# strobe_ds.net
KiCad netlist of a schematic drawn in EAGLE
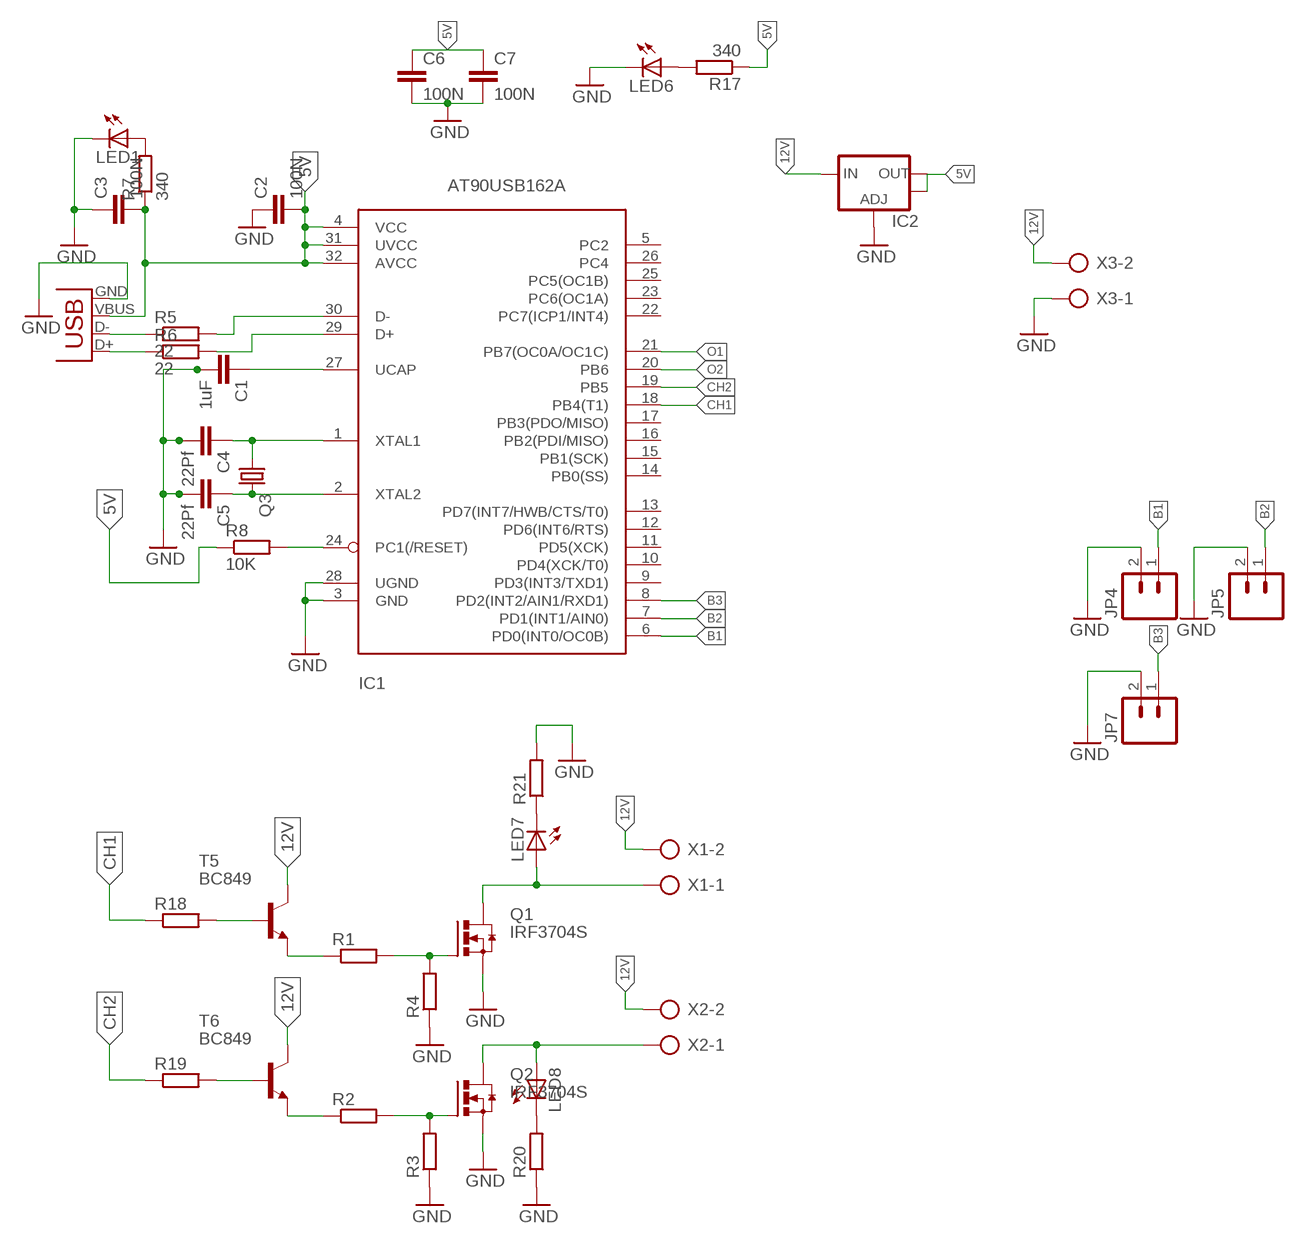
[diagram p0: schematic, sheet 1]

(export (version "E")
  (design (tool "Eeschema 10.0.6"))
  (components
    (comp (ref "C1")
      (value "1uF")
      (footprint "eagle-import:C0805")
      (libsource (lib "eagle-import") (part "C-EUC0805"))
    )
    (comp (ref "C2")
      (value "100N")
      (footprint "eagle-import:C0805")
      (libsource (lib "eagle-import") (part "C-EUC0805"))
    )
    (comp (ref "C3")
      (value "100N")
      (footprint "eagle-import:C0805")
      (libsource (lib "eagle-import") (part "C-EUC0805"))
    )
    (comp (ref "C4")
      (value "22Pf")
      (footprint "eagle-import:C0603")
      (libsource (lib "eagle-import") (part "C-EUC0603"))
    )
    (comp (ref "C5")
      (value "22Pf")
      (footprint "eagle-import:C0603")
      (libsource (lib "eagle-import") (part "C-EUC0603"))
    )
    (comp (ref "C6")
      (value "100N")
      (footprint "eagle-import:C0805")
      (libsource (lib "eagle-import") (part "C-EUC0805"))
    )
    (comp (ref "C7")
      (value "100N")
      (footprint "eagle-import:C0805")
      (libsource (lib "eagle-import") (part "C-EUC0805"))
    )
    (comp (ref "IC1")
      (value "AT90USB162A")
      (footprint "eagle-import:TQFP32-08")
      (libsource (lib "eagle-import") (part "AT90USB162A"))
    )
    (comp (ref "IC2")
      (value "V_REG_LM1117SOT223")
      (footprint "eagle-import:SOT223")
      (libsource (lib "eagle-import") (part "V_REG_LM1117SOT223"))
    )
    (comp (ref "JP1")
      (value "USBSMD")
      (footprint "eagle-import:USB-MINIB")
      (libsource (lib "eagle-import") (part "USBSMD"))
    )
    (comp (ref "JP4")
      (value "M02PTH3")
      (footprint "eagle-import:1X02_LONGPADS")
      (libsource (lib "eagle-import") (part "M02PTH3"))
    )
    (comp (ref "JP5")
      (value "M02PTH3")
      (footprint "eagle-import:1X02_LONGPADS")
      (libsource (lib "eagle-import") (part "M02PTH3"))
    )
    (comp (ref "JP7")
      (value "M02PTH3")
      (footprint "eagle-import:1X02_LONGPADS")
      (libsource (lib "eagle-import") (part "M02PTH3"))
    )
    (comp (ref "LED1")
      (value "LEDSML0805")
      (footprint "eagle-import:SML0805")
      (libsource (lib "eagle-import") (part "LEDSML0805"))
    )
    (comp (ref "LED6")
      (value "LEDSML0805")
      (footprint "eagle-import:SML0805")
      (libsource (lib "eagle-import") (part "LEDSML0805"))
    )
    (comp (ref "LED7")
      (value "LEDSML0805")
      (footprint "eagle-import:SML0805")
      (libsource (lib "eagle-import") (part "LEDSML0805"))
    )
    (comp (ref "LED8")
      (value "LEDSML0805")
      (footprint "eagle-import:SML0805")
      (libsource (lib "eagle-import") (part "LEDSML0805"))
    )
    (comp (ref "Q1")
      (value "IRF3704S")
      (footprint "eagle-import:D2PACK")
      (libsource (lib "eagle-import") (part "IRF3704S"))
    )
    (comp (ref "Q2")
      (value "IRF3704S")
      (footprint "eagle-import:D2PACK")
      (libsource (lib "eagle-import") (part "IRF3704S"))
    )
    (comp (ref "Q3")
      (value "CRYSTALSM49")
      (footprint "eagle-import:SM49")
      (libsource (lib "eagle-import") (part "CRYSTALSM49"))
    )
    (comp (ref "R1")
      (value "R-EU_R0805")
      (footprint "eagle-import:R0805")
      (libsource (lib "eagle-import") (part "R-EU_R0805"))
    )
    (comp (ref "R2")
      (value "R-EU_R0805")
      (footprint "eagle-import:R0805")
      (libsource (lib "eagle-import") (part "R-EU_R0805"))
    )
    (comp (ref "R3")
      (value "R-EU_R0805")
      (footprint "eagle-import:R0805")
      (libsource (lib "eagle-import") (part "R-EU_R0805"))
    )
    (comp (ref "R4")
      (value "R-EU_R0805")
      (footprint "eagle-import:R0805")
      (libsource (lib "eagle-import") (part "R-EU_R0805"))
    )
    (comp (ref "R5")
      (value "22")
      (footprint "eagle-import:R0805")
      (libsource (lib "eagle-import") (part "R-EU_R0805"))
    )
    (comp (ref "R6")
      (value "22")
      (footprint "eagle-import:R0805")
      (libsource (lib "eagle-import") (part "R-EU_R0805"))
    )
    (comp (ref "R7")
      (value "340")
      (footprint "eagle-import:R0805")
      (libsource (lib "eagle-import") (part "R-EU_R0805"))
    )
    (comp (ref "R8")
      (value "10K")
      (footprint "eagle-import:R0805")
      (libsource (lib "eagle-import") (part "R-EU_R0805"))
    )
    (comp (ref "R17")
      (value "340")
      (footprint "eagle-import:R0805")
      (libsource (lib "eagle-import") (part "R-EU_R0805"))
    )
    (comp (ref "R18")
      (value "R-EU_R0805")
      (footprint "eagle-import:R0805")
      (libsource (lib "eagle-import") (part "R-EU_R0805"))
    )
    (comp (ref "R19")
      (value "R-EU_R0805")
      (footprint "eagle-import:R0805")
      (libsource (lib "eagle-import") (part "R-EU_R0805"))
    )
    (comp (ref "R20")
      (value "R-EU_R0805")
      (footprint "eagle-import:R0805")
      (libsource (lib "eagle-import") (part "R-EU_R0805"))
    )
    (comp (ref "R21")
      (value "R-EU_R0805")
      (footprint "eagle-import:R0805")
      (libsource (lib "eagle-import") (part "R-EU_R0805"))
    )
    (comp (ref "T5")
      (value "BC849")
      (footprint "eagle-import:SOT23")
      (libsource (lib "eagle-import") (part "BC849"))
    )
    (comp (ref "T6")
      (value "BC849")
      (footprint "eagle-import:SOT23")
      (libsource (lib "eagle-import") (part "BC849"))
    )
    (comp (ref "X1")
      (value "AK300/2")
      (footprint "eagle-import:AK300_2")
      (libsource (lib "eagle-import") (part "AK300/2"))
    )
    (comp (ref "X2")
      (value "AK300/2")
      (footprint "eagle-import:AK300_2")
      (libsource (lib "eagle-import") (part "AK300/2"))
    )
    (comp (ref "X3")
      (value "AK300/2")
      (footprint "eagle-import:AK300_2")
      (libsource (lib "eagle-import") (part "AK300/2"))
    )
  )
  (nets
    (net (code "1") (name "5V") (class "Default")
      (node (ref "C2") (pin "2") (pinfunction "2_2") (pintype "passive"))
      (node (ref "C3") (pin "2") (pinfunction "2_2") (pintype "passive"))
      (node (ref "C6") (pin "1") (pinfunction "1_1") (pintype "passive"))
      (node (ref "C7") (pin "1") (pinfunction "1_1") (pintype "passive"))
      (node (ref "IC1") (pin "31") (pinfunction "UVCC_31") (pintype "bidirectional"))
      (node (ref "IC1") (pin "32") (pinfunction "AVCC_32") (pintype "bidirectional"))
      (node (ref "IC1") (pin "4") (pinfunction "VCC_4") (pintype "bidirectional"))
      (node (ref "IC2") (pin "2") (pinfunction "OUT_2") (pintype "output"))
      (node (ref "IC2") (pin "4") (pinfunction "OUT_4") (pintype "output"))
      (node (ref "JP1") (pin "VBUS") (pinfunction "VBUS_VBUS") (pintype "bidirectional"))
      (node (ref "R17") (pin "1") (pinfunction "1_1") (pintype "passive"))
      (node (ref "R7") (pin "1") (pinfunction "1_1") (pintype "passive"))
      (node (ref "R8") (pin "1") (pinfunction "1_1") (pintype "passive"))
    )
    (net (code "2") (name "12V") (class "Default")
      (node (ref "IC2") (pin "3") (pinfunction "IN_3") (pintype "input"))
      (node (ref "T5") (pin "3") (pinfunction "C_3") (pintype "passive"))
      (node (ref "T6") (pin "3") (pinfunction "C_3") (pintype "passive"))
      (node (ref "X1") (pin "2") (pinfunction "KL_2") (pintype "passive"))
      (node (ref "X2") (pin "2") (pinfunction "KL_2") (pintype "passive"))
      (node (ref "X3") (pin "2") (pinfunction "KL_2") (pintype "passive"))
    )
    (net (code "3") (name "B1") (class "Default")
      (node (ref "IC1") (pin "6") (pinfunction "PD0(INT0/OC0B)_6") (pintype "bidirectional"))
      (node (ref "JP4") (pin "1") (pinfunction "1_1") (pintype "passive"))
    )
    (net (code "4") (name "B2") (class "Default")
      (node (ref "IC1") (pin "7") (pinfunction "PD1(INT1/AIN0)_7") (pintype "bidirectional"))
      (node (ref "JP5") (pin "1") (pinfunction "1_1") (pintype "passive"))
    )
    (net (code "5") (name "B3") (class "Default")
      (node (ref "IC1") (pin "8") (pinfunction "PD2(INT2/AIN1/RXD1)_8") (pintype "bidirectional"))
      (node (ref "JP7") (pin "1") (pinfunction "1_1") (pintype "passive"))
    )
    (net (code "6") (name "CH1") (class "Default")
      (node (ref "IC1") (pin "18") (pinfunction "PB4(T1)_18") (pintype "bidirectional"))
      (node (ref "R18") (pin "1") (pinfunction "1_1") (pintype "passive"))
    )
    (net (code "7") (name "CH2") (class "Default")
      (node (ref "IC1") (pin "19") (pinfunction "PB5_19") (pintype "bidirectional"))
      (node (ref "R19") (pin "1") (pinfunction "1_1") (pintype "passive"))
    )
    (net (code "8") (name "GND") (class "Default")
      (node (ref "C1") (pin "2") (pinfunction "2_2") (pintype "passive"))
      (node (ref "C2") (pin "1") (pinfunction "1_1") (pintype "passive"))
      (node (ref "C3") (pin "1") (pinfunction "1_1") (pintype "passive"))
      (node (ref "C4") (pin "2") (pinfunction "2_2") (pintype "passive"))
      (node (ref "C5") (pin "2") (pinfunction "2_2") (pintype "passive"))
      (node (ref "C6") (pin "2") (pinfunction "2_2") (pintype "passive"))
      (node (ref "C7") (pin "2") (pinfunction "2_2") (pintype "passive"))
      (node (ref "IC1") (pin "28") (pinfunction "UGND_28") (pintype "bidirectional"))
      (node (ref "IC1") (pin "3") (pinfunction "GND_3") (pintype "bidirectional"))
      (node (ref "IC2") (pin "1") (pinfunction "ADJ_1") (pintype "input"))
      (node (ref "JP1") (pin "GND") (pinfunction "GND_GND") (pintype "bidirectional"))
      (node (ref "JP4") (pin "2") (pinfunction "2_2") (pintype "passive"))
      (node (ref "JP5") (pin "2") (pinfunction "2_2") (pintype "passive"))
      (node (ref "JP7") (pin "2") (pinfunction "2_2") (pintype "passive"))
      (node (ref "LED1") (pin "C") (pinfunction "C_C") (pintype "passive"))
      (node (ref "LED6") (pin "C") (pinfunction "C_C") (pintype "passive"))
      (node (ref "Q1") (pin "3") (pinfunction "S_3") (pintype "passive"))
      (node (ref "Q2") (pin "3") (pinfunction "S_3") (pintype "passive"))
      (node (ref "R20") (pin "1") (pinfunction "1_1") (pintype "passive"))
      (node (ref "R21") (pin "2") (pinfunction "2_2") (pintype "passive"))
      (node (ref "R3") (pin "1") (pinfunction "1_1") (pintype "passive"))
      (node (ref "R4") (pin "1") (pinfunction "1_1") (pintype "passive"))
      (node (ref "X3") (pin "1") (pinfunction "KL_1") (pintype "passive"))
    )
    (net (code "9") (name "Net-(IC1-D+)") (class "Default")
      (node (ref "IC1") (pin "29") (pinfunction "D+_29") (pintype "bidirectional"))
      (node (ref "R6") (pin "2") (pinfunction "2_2") (pintype "passive"))
    )
    (net (code "10") (name "Net-(IC1-D-)") (class "Default")
      (node (ref "IC1") (pin "30") (pinfunction "D-_30") (pintype "bidirectional"))
      (node (ref "R5") (pin "2") (pinfunction "2_2") (pintype "passive"))
    )
    (net (code "11") (name "Net-(IC1-PC1({slash}RESET))") (class "Default")
      (node (ref "IC1") (pin "24") (pinfunction "PC1(/RESET)_24") (pintype "bidirectional"))
      (node (ref "R8") (pin "2") (pinfunction "2_2") (pintype "passive"))
    )
    (net (code "12") (name "Net-(IC1-UCAP)") (class "Default")
      (node (ref "C1") (pin "1") (pinfunction "1_1") (pintype "passive"))
      (node (ref "IC1") (pin "27") (pinfunction "UCAP_27") (pintype "bidirectional"))
    )
    (net (code "13") (name "Net-(IC1-XTAL1)") (class "Default")
      (node (ref "C4") (pin "1") (pinfunction "1_1") (pintype "passive"))
      (node (ref "IC1") (pin "1") (pinfunction "XTAL1_1") (pintype "bidirectional"))
      (node (ref "Q3") (pin "1") (pinfunction "1_1") (pintype "passive"))
    )
    (net (code "14") (name "Net-(IC1-XTAL2)") (class "Default")
      (node (ref "C5") (pin "1") (pinfunction "1_1") (pintype "passive"))
      (node (ref "IC1") (pin "2") (pinfunction "XTAL2_2") (pintype "bidirectional"))
      (node (ref "Q3") (pin "2") (pinfunction "2_2") (pintype "passive"))
    )
    (net (code "15") (name "Net-(JP1-PadD+)") (class "Default")
      (node (ref "JP1") (pin "D+") (pinfunction "D+_D+") (pintype "bidirectional"))
      (node (ref "R6") (pin "1") (pinfunction "1_1") (pintype "passive"))
    )
    (net (code "16") (name "Net-(JP1-PadD-)") (class "Default")
      (node (ref "JP1") (pin "D-") (pinfunction "D-_D-") (pintype "bidirectional"))
      (node (ref "R5") (pin "1") (pinfunction "1_1") (pintype "passive"))
    )
    (net (code "17") (name "Net-(LED1-PadA)") (class "Default")
      (node (ref "LED1") (pin "A") (pinfunction "A_A") (pintype "passive"))
      (node (ref "R7") (pin "2") (pinfunction "2_2") (pintype "passive"))
    )
    (net (code "18") (name "Net-(LED6-PadA)") (class "Default")
      (node (ref "LED6") (pin "A") (pinfunction "A_A") (pintype "passive"))
      (node (ref "R17") (pin "2") (pinfunction "2_2") (pintype "passive"))
    )
    (net (code "19") (name "Net-(LED7-PadC)") (class "Default")
      (node (ref "LED7") (pin "C") (pinfunction "C_C") (pintype "passive"))
      (node (ref "R21") (pin "1") (pinfunction "1_1") (pintype "passive"))
    )
    (net (code "20") (name "Net-(LED8-PadC)") (class "Default")
      (node (ref "LED8") (pin "C") (pinfunction "C_C") (pintype "passive"))
      (node (ref "R20") (pin "2") (pinfunction "2_2") (pintype "passive"))
    )
    (net (code "21") (name "Net-(Q1-D)") (class "Default")
      (node (ref "LED7") (pin "A") (pinfunction "A_A") (pintype "passive"))
      (node (ref "Q1") (pin "2") (pinfunction "D_2") (pintype "passive"))
      (node (ref "X1") (pin "1") (pinfunction "KL_1") (pintype "passive"))
    )
    (net (code "22") (name "Net-(Q1-G)") (class "Default")
      (node (ref "Q1") (pin "1") (pinfunction "G_1") (pintype "passive"))
      (node (ref "R1") (pin "2") (pinfunction "2_2") (pintype "passive"))
      (node (ref "R4") (pin "2") (pinfunction "2_2") (pintype "passive"))
    )
    (net (code "23") (name "Net-(Q2-D)") (class "Default")
      (node (ref "LED8") (pin "A") (pinfunction "A_A") (pintype "passive"))
      (node (ref "Q2") (pin "2") (pinfunction "D_2") (pintype "passive"))
      (node (ref "X2") (pin "1") (pinfunction "KL_1") (pintype "passive"))
    )
    (net (code "24") (name "Net-(Q2-G)") (class "Default")
      (node (ref "Q2") (pin "1") (pinfunction "G_1") (pintype "passive"))
      (node (ref "R2") (pin "2") (pinfunction "2_2") (pintype "passive"))
      (node (ref "R3") (pin "2") (pinfunction "2_2") (pintype "passive"))
    )
    (net (code "25") (name "Net-(T5-B)") (class "Default")
      (node (ref "R18") (pin "2") (pinfunction "2_2") (pintype "passive"))
      (node (ref "T5") (pin "1") (pinfunction "B_1") (pintype "passive"))
    )
    (net (code "26") (name "Net-(T5-E)") (class "Default")
      (node (ref "R1") (pin "1") (pinfunction "1_1") (pintype "passive"))
      (node (ref "T5") (pin "2") (pinfunction "E_2") (pintype "passive"))
    )
    (net (code "27") (name "Net-(T6-B)") (class "Default")
      (node (ref "R19") (pin "2") (pinfunction "2_2") (pintype "passive"))
      (node (ref "T6") (pin "1") (pinfunction "B_1") (pintype "passive"))
    )
    (net (code "28") (name "Net-(T6-E)") (class "Default")
      (node (ref "R2") (pin "1") (pinfunction "1_1") (pintype "passive"))
      (node (ref "T6") (pin "2") (pinfunction "E_2") (pintype "passive"))
    )
    (net (code "29") (name "O1") (class "Default")
      (node (ref "IC1") (pin "21") (pinfunction "PB7(OC0A/OC1C)_21") (pintype "bidirectional"))
    )
    (net (code "30") (name "O2") (class "Default")
      (node (ref "IC1") (pin "20") (pinfunction "PB6_20") (pintype "bidirectional"))
    )
    (net (code "31") (name "unconnected-(IC1-PB0(SS)-Pad14)") (class "Default")
      (node (ref "IC1") (pin "14") (pinfunction "PB0(SS)_14") (pintype "bidirectional"))
    )
    (net (code "32") (name "unconnected-(IC1-PB1(SCK)-Pad15)") (class "Default")
      (node (ref "IC1") (pin "15") (pinfunction "PB1(SCK)_15") (pintype "bidirectional"))
    )
    (net (code "33") (name "unconnected-(IC1-PB2(PDI{slash}MISO)-Pad16)") (class "Default")
      (node (ref "IC1") (pin "16") (pinfunction "PB2(PDI/MISO)_16") (pintype "bidirectional"))
    )
    (net (code "34") (name "unconnected-(IC1-PB3(PDO{slash}MISO)-Pad17)") (class "Default")
      (node (ref "IC1") (pin "17") (pinfunction "PB3(PDO/MISO)_17") (pintype "bidirectional"))
    )
    (net (code "35") (name "unconnected-(IC1-PC2-Pad5)") (class "Default")
      (node (ref "IC1") (pin "5") (pinfunction "PC2_5") (pintype "bidirectional"))
    )
    (net (code "36") (name "unconnected-(IC1-PC4-Pad26)") (class "Default")
      (node (ref "IC1") (pin "26") (pinfunction "PC4_26") (pintype "bidirectional"))
    )
    (net (code "37") (name "unconnected-(IC1-PC5(OC1B)-Pad25)") (class "Default")
      (node (ref "IC1") (pin "25") (pinfunction "PC5(OC1B)_25") (pintype "bidirectional"))
    )
    (net (code "38") (name "unconnected-(IC1-PC6(OC1A)-Pad23)") (class "Default")
      (node (ref "IC1") (pin "23") (pinfunction "PC6(OC1A)_23") (pintype "bidirectional"))
    )
    (net (code "39") (name "unconnected-(IC1-PC7(ICP1{slash}INT4)-Pad22)") (class "Default")
      (node (ref "IC1") (pin "22") (pinfunction "PC7(ICP1/INT4)_22") (pintype "bidirectional"))
    )
    (net (code "40") (name "unconnected-(IC1-PD3(INT3{slash}TXD1)-Pad9)") (class "Default")
      (node (ref "IC1") (pin "9") (pinfunction "PD3(INT3/TXD1)_9") (pintype "bidirectional"))
    )
    (net (code "41") (name "unconnected-(IC1-PD4(XCK{slash}T0)-Pad10)") (class "Default")
      (node (ref "IC1") (pin "10") (pinfunction "PD4(XCK/T0)_10") (pintype "bidirectional"))
    )
    (net (code "42") (name "unconnected-(IC1-PD5(XCK)-Pad11)") (class "Default")
      (node (ref "IC1") (pin "11") (pinfunction "PD5(XCK)_11") (pintype "bidirectional"))
    )
    (net (code "43") (name "unconnected-(IC1-PD6(INT6{slash}RTS)-Pad12)") (class "Default")
      (node (ref "IC1") (pin "12") (pinfunction "PD6(INT6/RTS)_12") (pintype "bidirectional"))
    )
    (net (code "44") (name "unconnected-(IC1-PD7(INT7{slash}HWB{slash}CTS{slash}T0)-Pad13)") (class "Default")
      (node (ref "IC1") (pin "13") (pinfunction "PD7(INT7/HWB/CTS/T0)_13") (pintype "bidirectional"))
    )
  )
)
